# RMP_-_HALF_BRIDGE_0_0_2.net
KiCad netlist of a schematic drawn in EAGLE
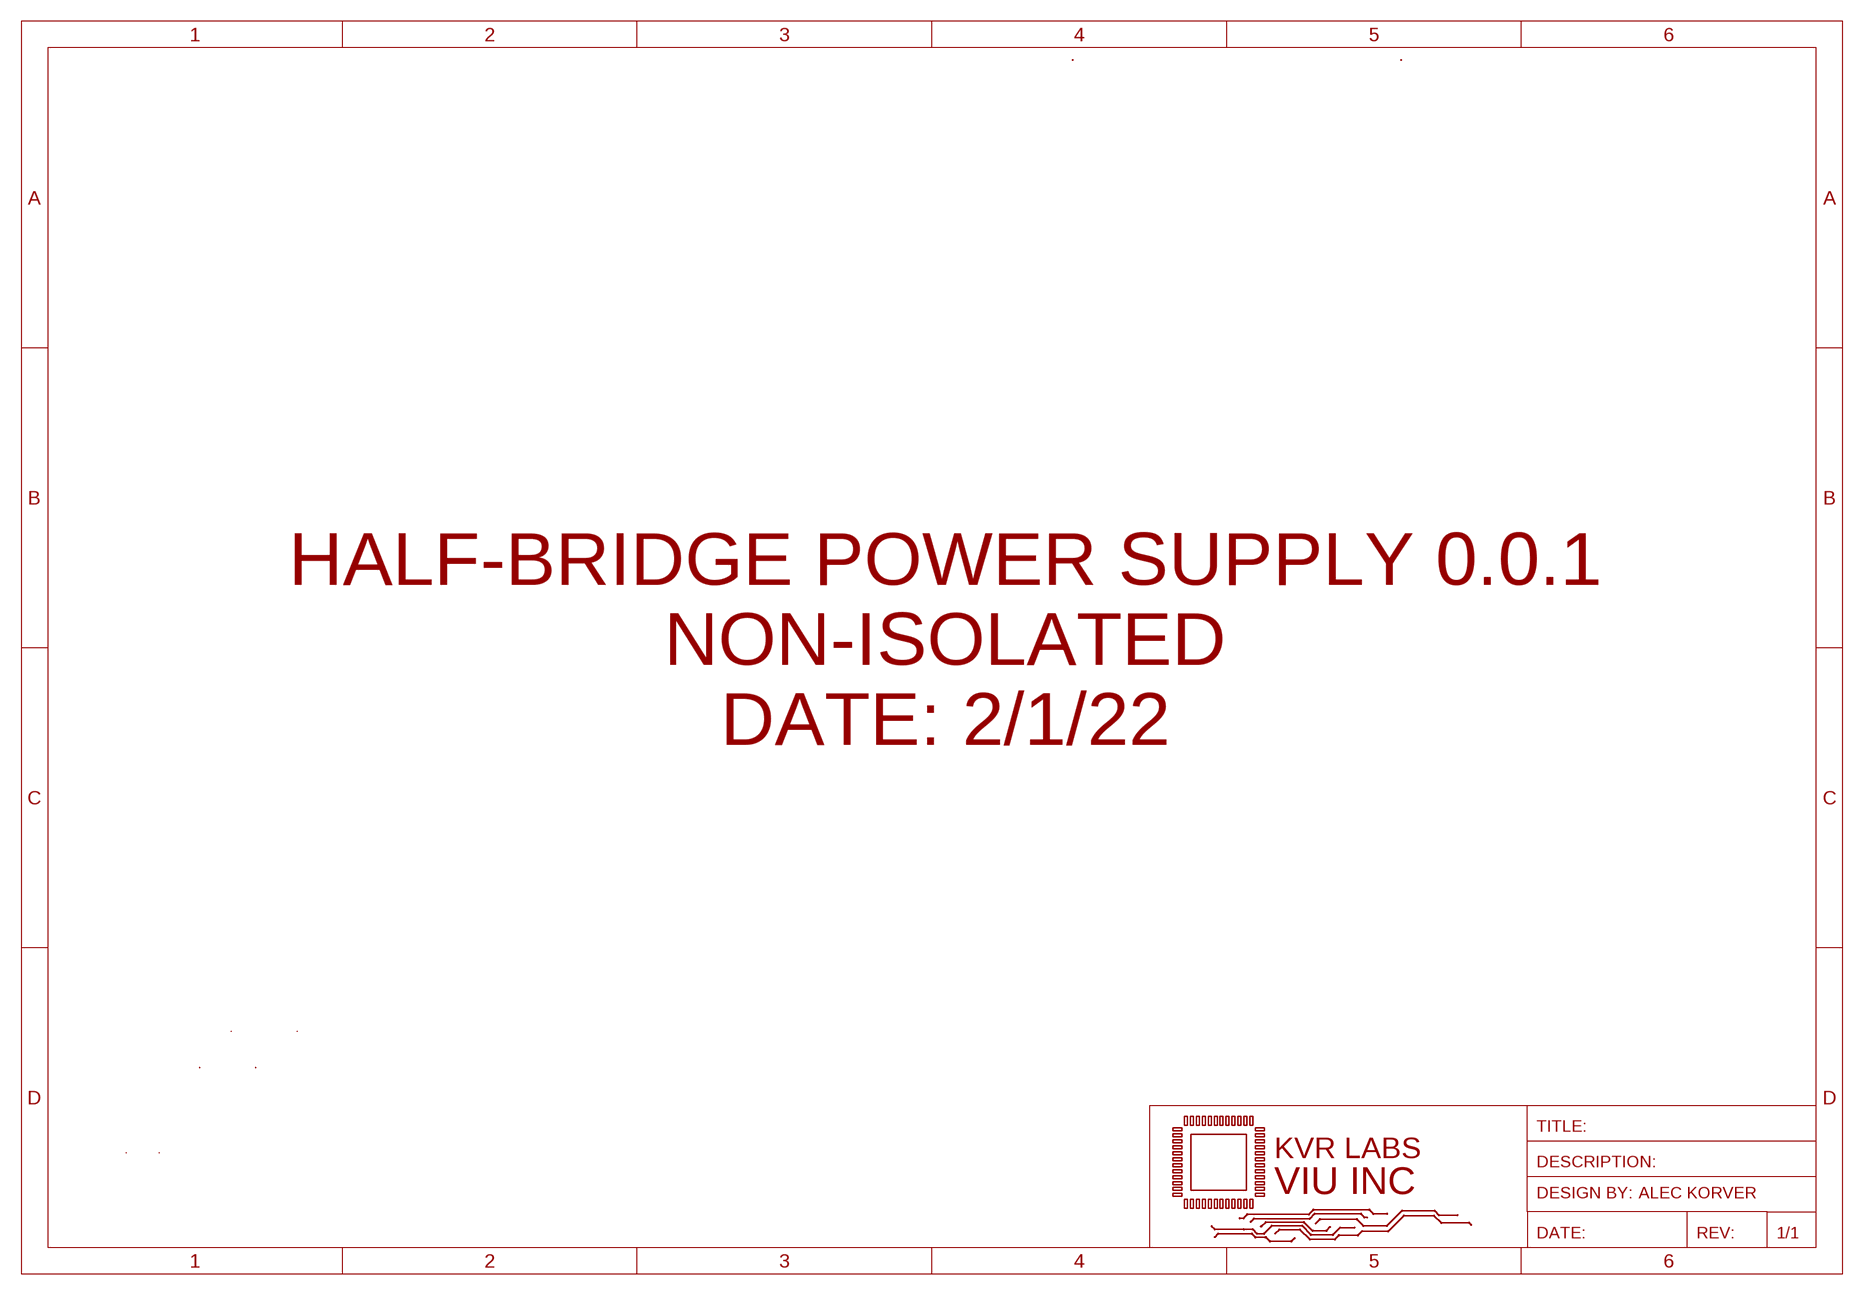
[diagram p0: schematic, sheet 1]
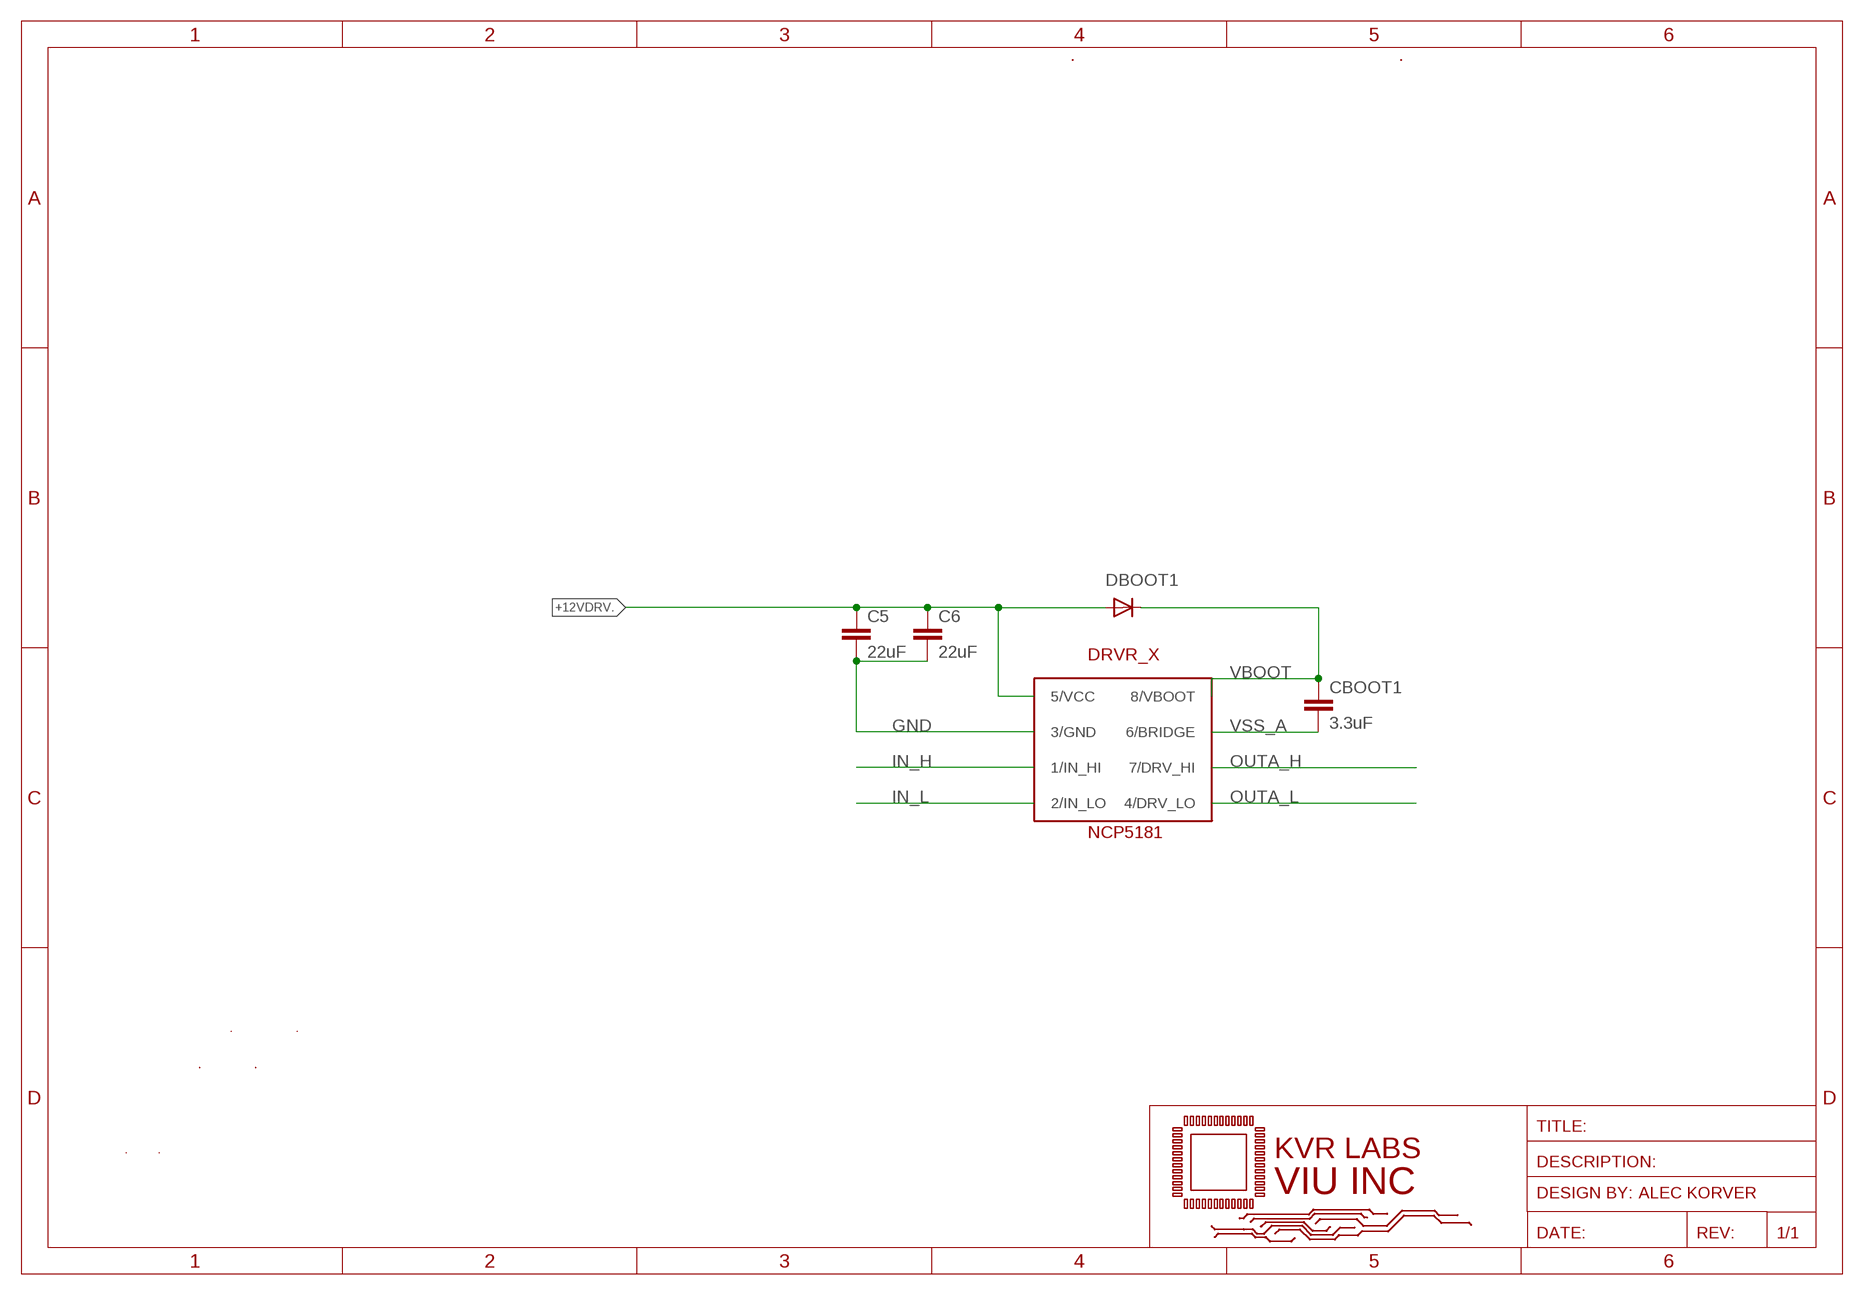
[diagram p1: schematic, sheet 2]
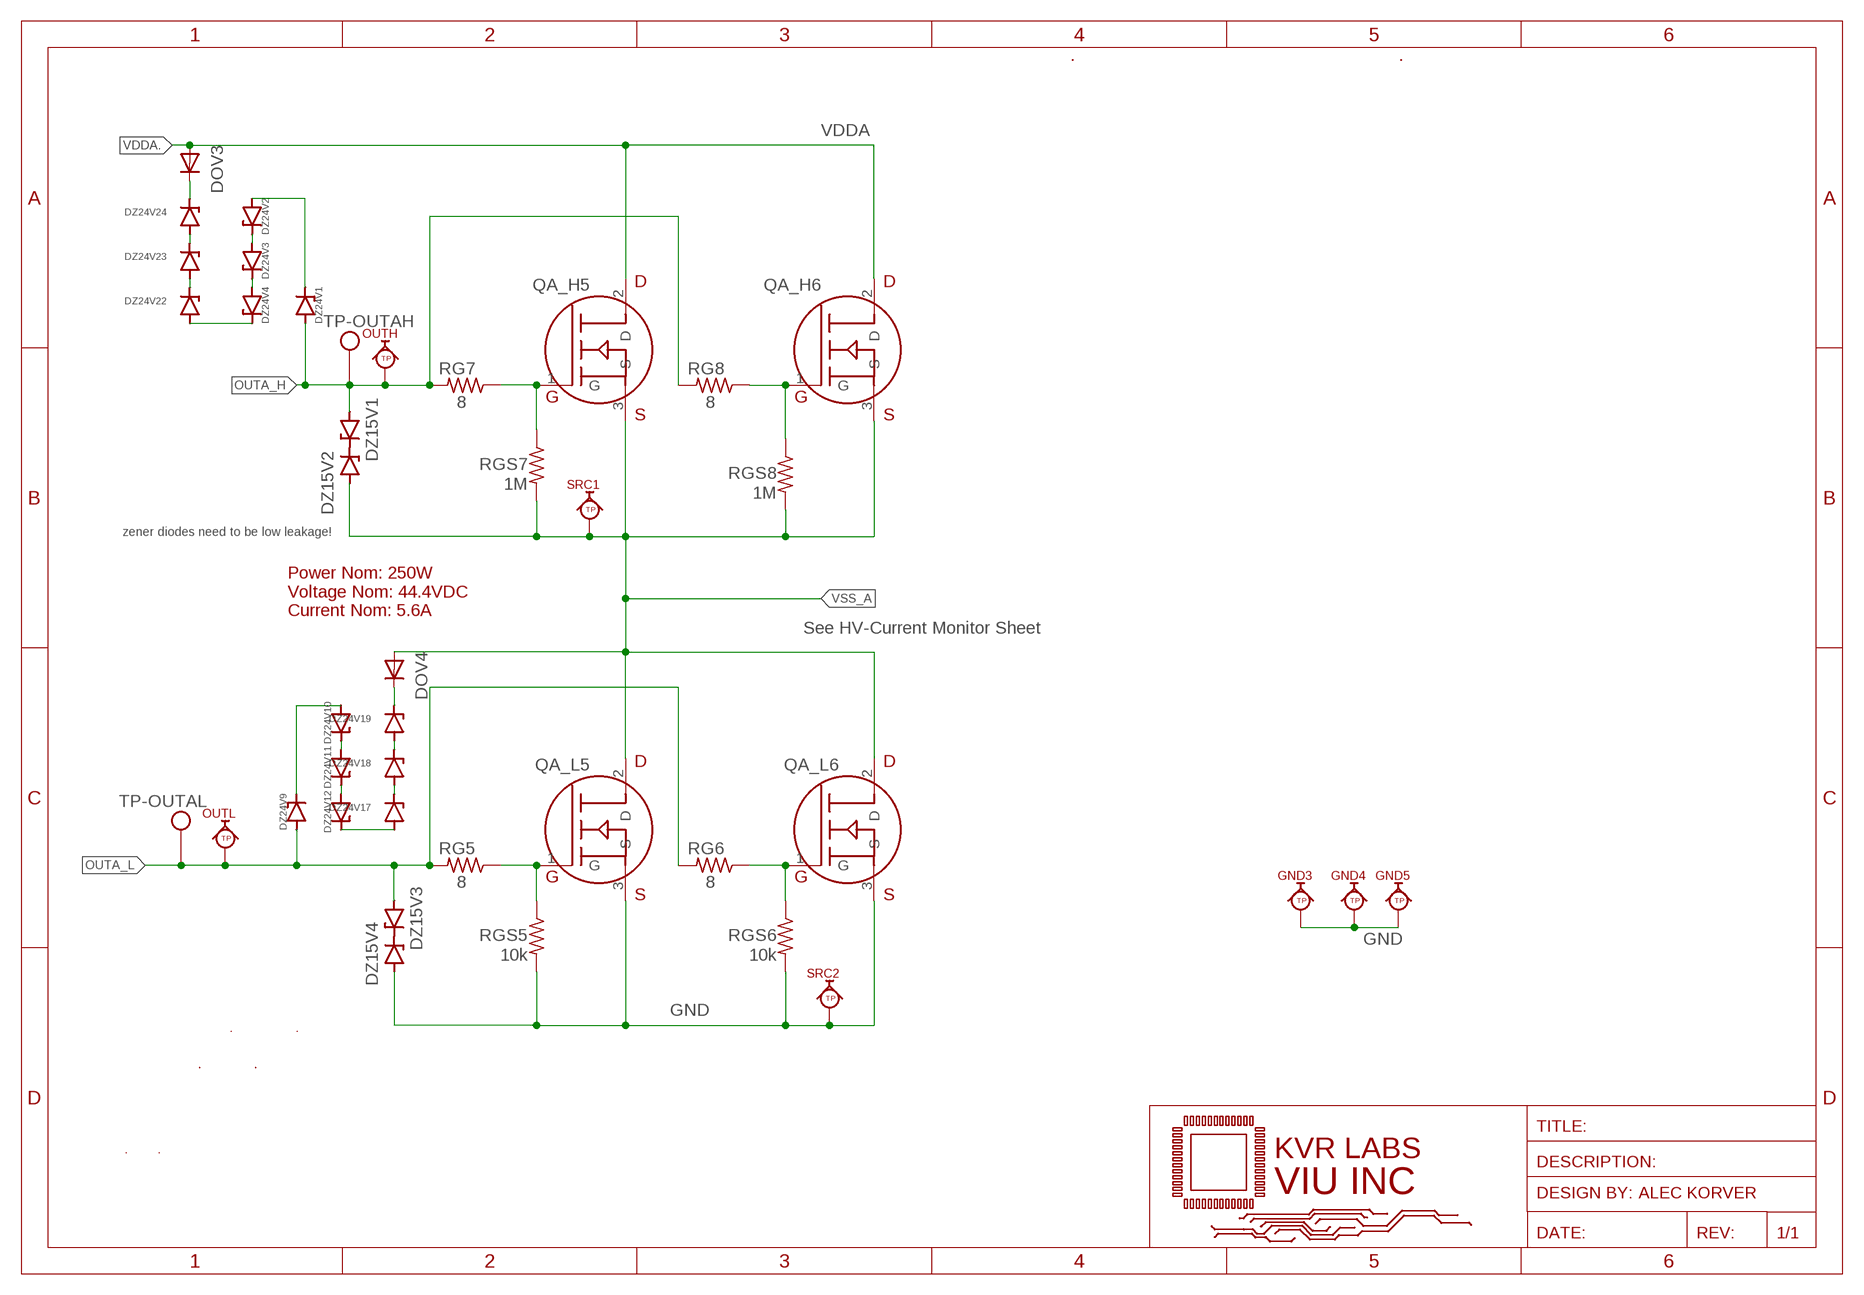
[diagram p2: schematic, sheet 3]
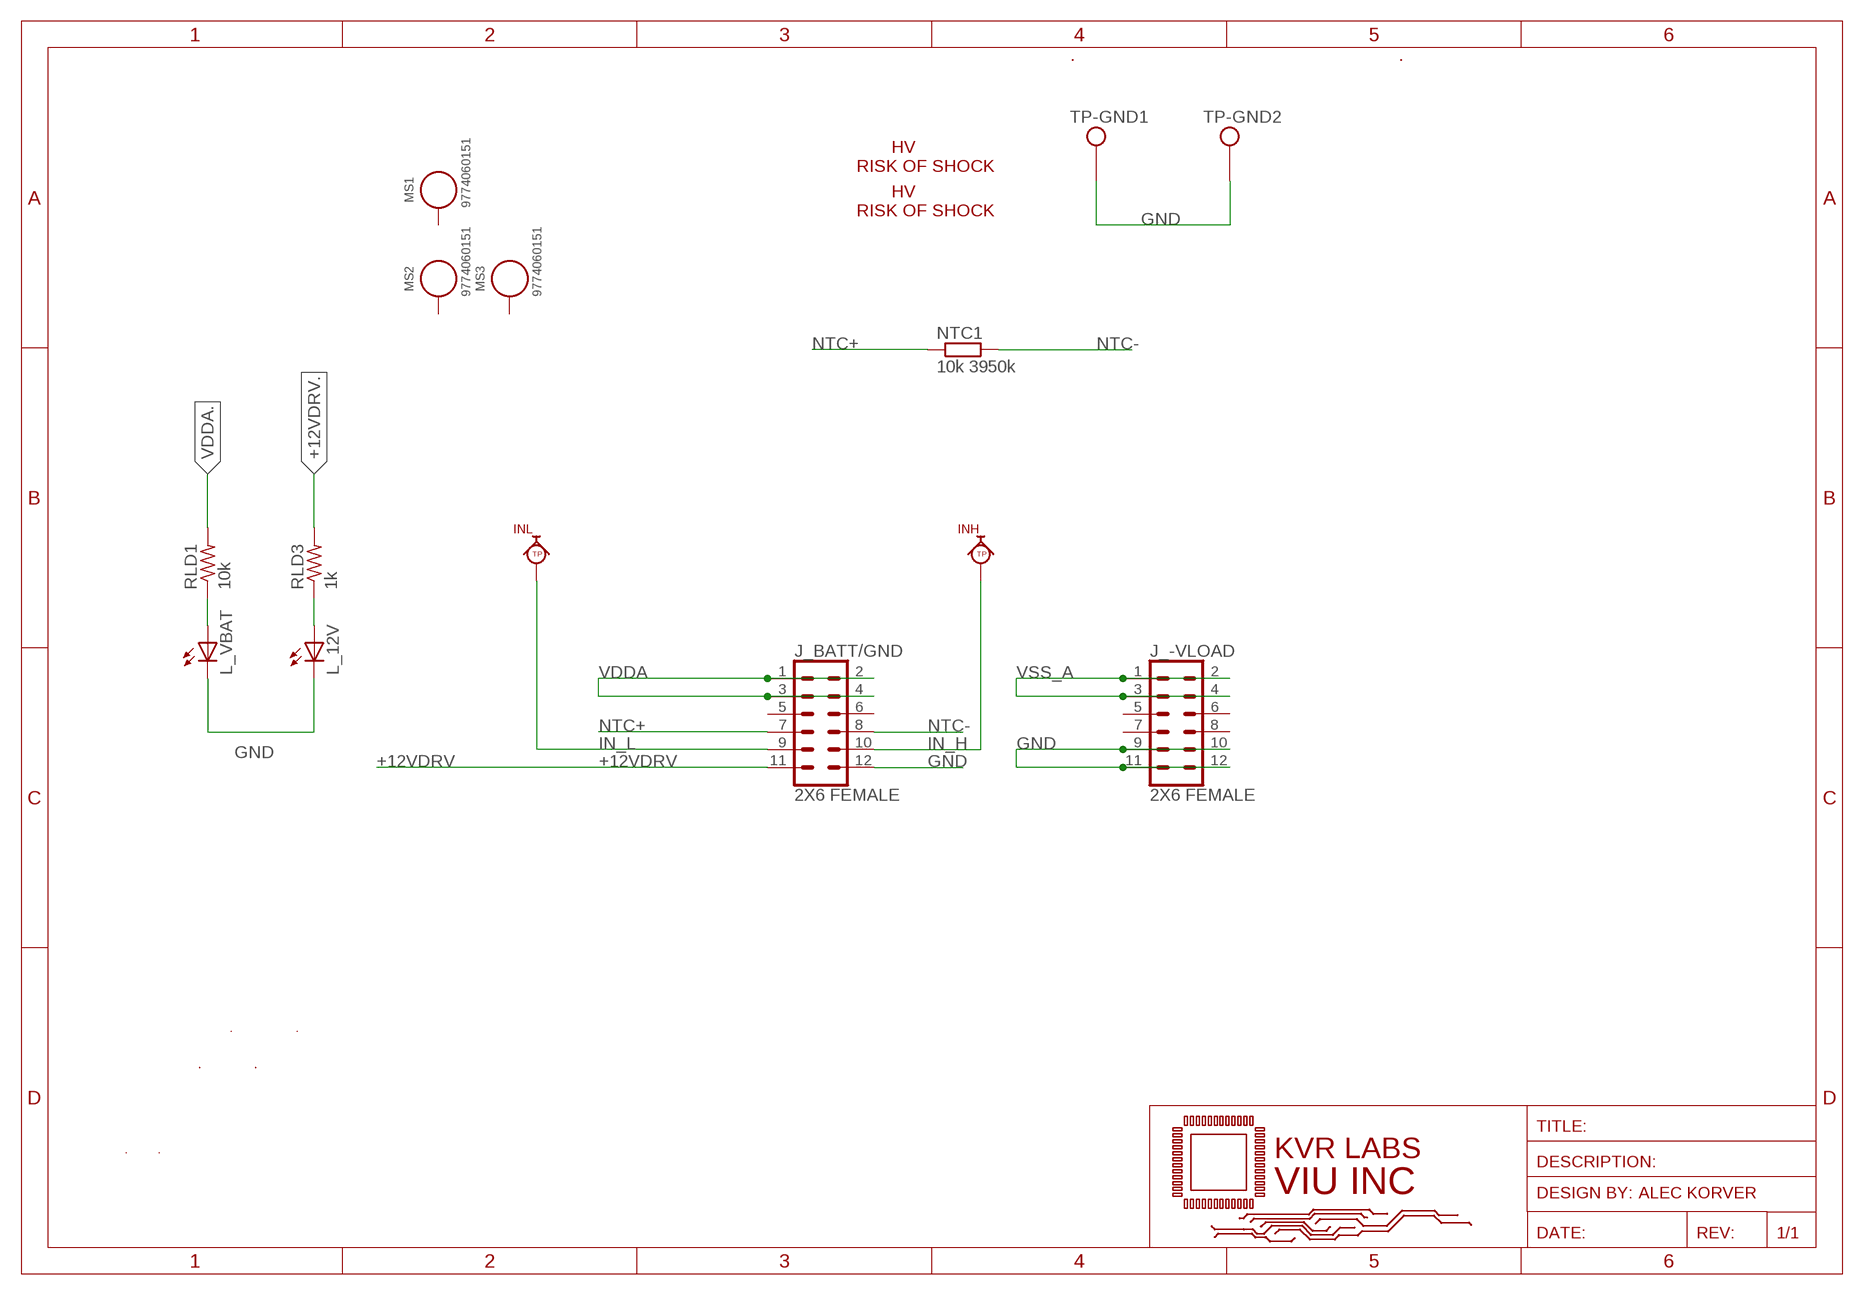
[diagram p3: schematic, sheet 4]
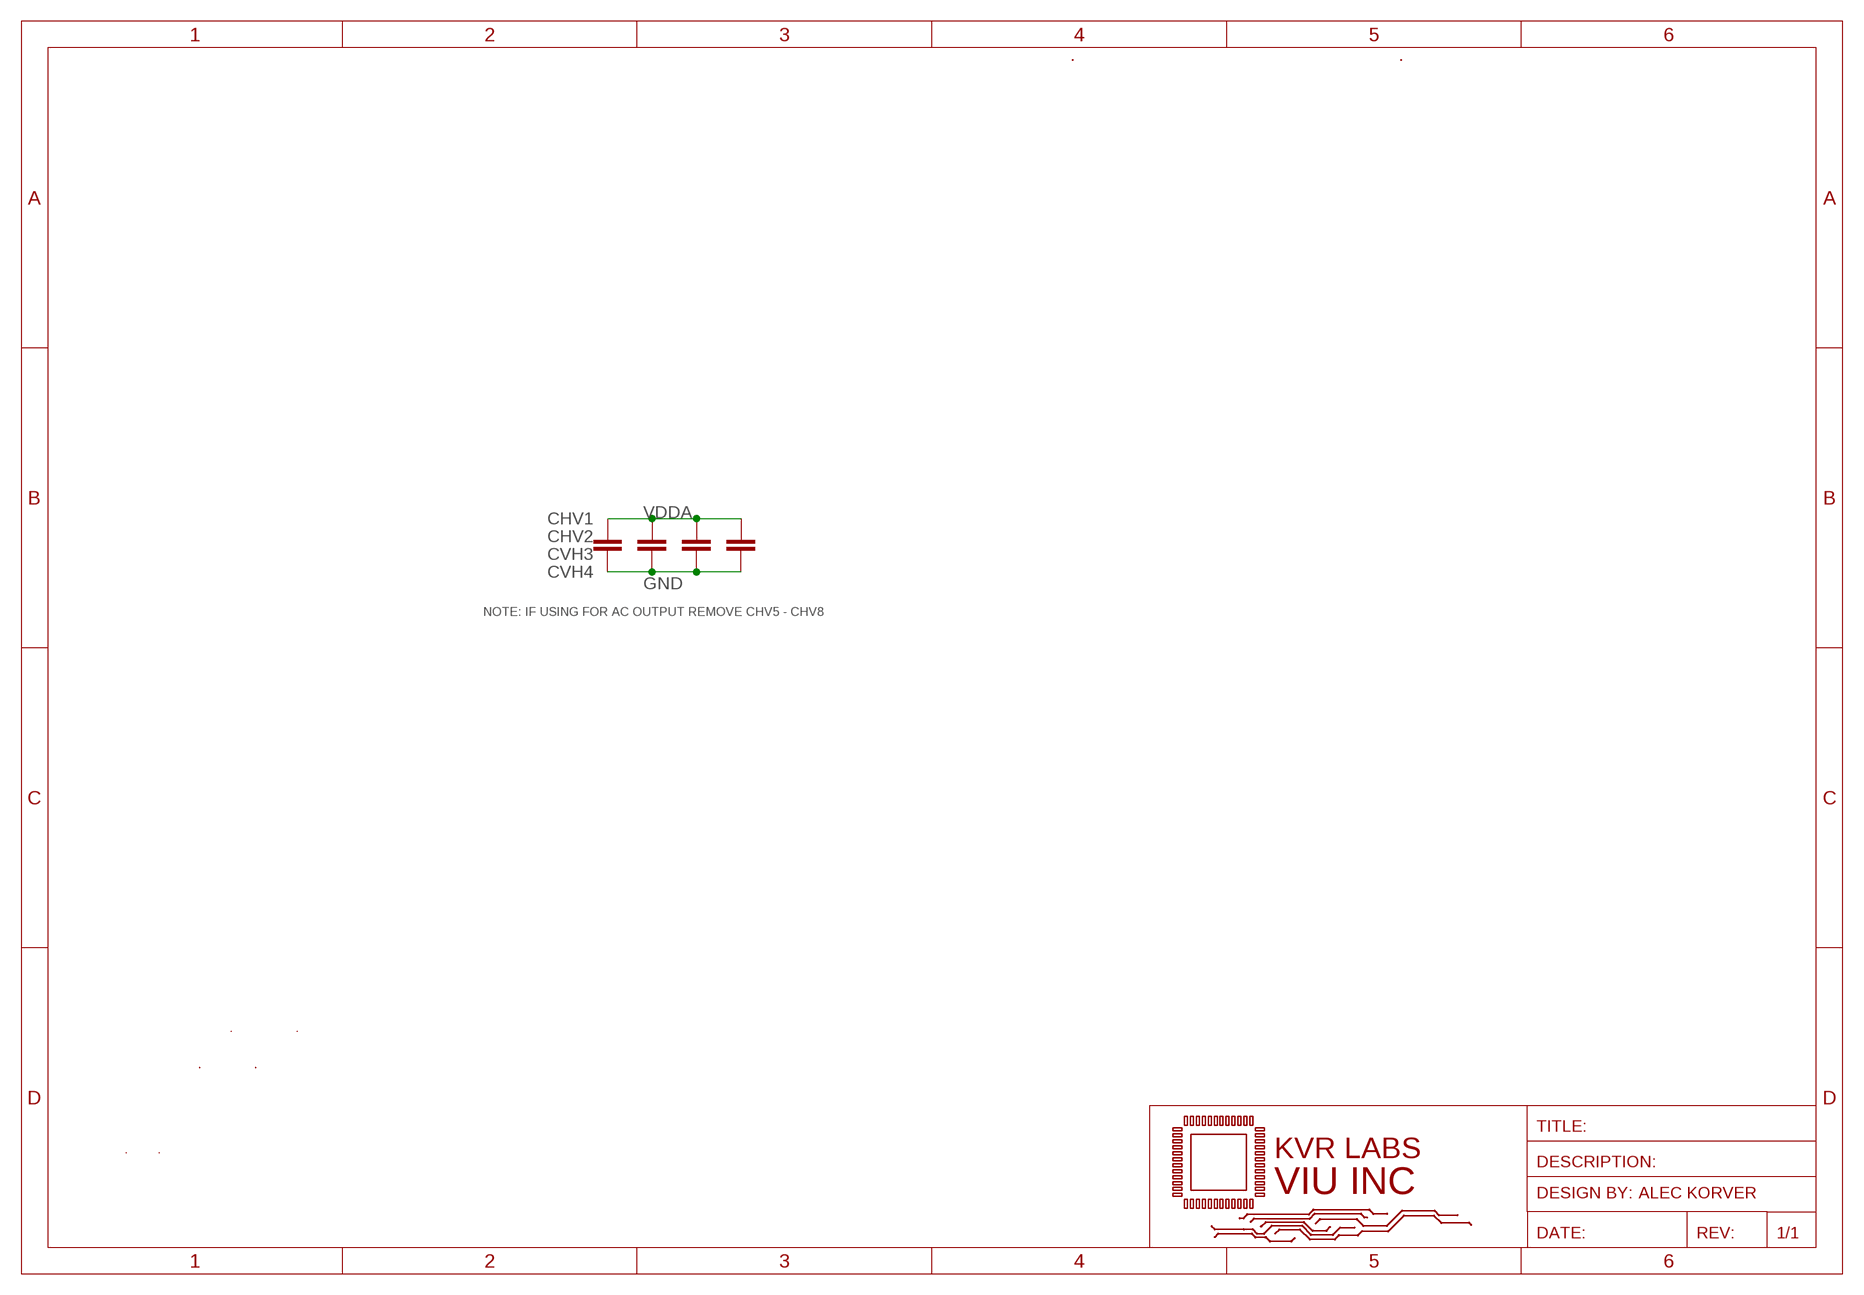
[diagram p4: schematic, sheet 5]

(export (version "E")
  (design (tool "Eeschema 10.0.6"))
  (components
    (comp (ref "INH")
      (value "KEYSTONE_5190_SMT")
      (footprint "eagle-import:KEYSTONE_5190_SMT")
      (libsource (lib "eagle-import") (part "KEYSTONE_5190_SMT"))
    )
    (comp (ref "INL")
      (value "KEYSTONE_5190_SMT")
      (footprint "eagle-import:KEYSTONE_5190_SMT")
      (libsource (lib "eagle-import") (part "KEYSTONE_5190_SMT"))
    )
    (comp (ref "J_-VLOAD")
      (value "2X6 FEMALE")
      (footprint "eagle-import:2X6")
      (fields (field (name "LCSC_PART") "DNP"))
      (libsource (lib "eagle-import") (part "CONN_06X2PTH_FEMALE"))
    )
    (comp (ref "J_BATT/GND")
      (value "2X6 FEMALE")
      (footprint "eagle-import:2X6")
      (fields (field (name "LCSC_PART") "DNP"))
      (libsource (lib "eagle-import") (part "CONN_06X2PTH_FEMALE"))
    )
    (comp (ref "L_12V")
      (value "LEDCHIPLED_1206")
      (footprint "eagle-import:CHIPLED_1206")
      (fields (field (name "LCSC_PART") "C434439"))
      (libsource (lib "eagle-import") (part "LEDCHIPLED_1206"))
    )
    (comp (ref "L_VBAT")
      (value "LEDCHIPLED_1206")
      (footprint "eagle-import:CHIPLED_1206")
      (fields (field (name "LCSC_PART") "C434439"))
      (libsource (lib "eagle-import") (part "LEDCHIPLED_1206"))
    )
    (comp (ref "MS1")
      (value "9774060151")
      (footprint "eagle-import:WA-SMSI_9774060151")
      (fields (field (name "LCSC_PART") "DNP"))
      (libsource (lib "eagle-import") (part "WA-SMSI_9774XXX151_9774060151"))
    )
    (comp (ref "MS2")
      (value "9774060151")
      (footprint "eagle-import:WA-SMSI_9774060151")
      (fields (field (name "LCSC_PART") "DNP"))
      (libsource (lib "eagle-import") (part "WA-SMSI_9774XXX151_9774060151"))
    )
    (comp (ref "MS3")
      (value "9774060151")
      (footprint "eagle-import:WA-SMSI_9774060151")
      (fields (field (name "LCSC_PART") "DNP"))
      (libsource (lib "eagle-import") (part "WA-SMSI_9774XXX151_9774060151"))
    )
    (comp (ref "NTC1")
      (value "10k 3950k")
      (footprint "eagle-import:R0805")
      (fields (field (name "LCSC_PART") "C95968"))
      (libsource (lib "eagle-import") (part "R-EU_R0805"))
    )
    (comp (ref "RLD1")
      (value "10k")
      (footprint "eagle-import:R1206")
      (fields (field (name "LCSC_PART") "C140407"))
      (libsource (lib "eagle-import") (part "R-US_R1206"))
    )
    (comp (ref "RLD3")
      (value "1k")
      (footprint "eagle-import:R1206")
      (fields (field (name "LCSC_PART") "C115421"))
      (libsource (lib "eagle-import") (part "R-US_R1206"))
    )
    (comp (ref "TP-GND1")
      (value "THM_TESTPOINT_5000_SERIES")
      (footprint "eagle-import:THM-TESTPOINT")
      (fields (field (name "LCSC_PART") "DNP"))
      (libsource (lib "eagle-import") (part "THM_TESTPOINT_5000_SERIES"))
    )
    (comp (ref "TP-GND2")
      (value "THM_TESTPOINT_5000_SERIES")
      (footprint "eagle-import:THM-TESTPOINT")
      (fields (field (name "LCSC_PART") "DNP"))
      (libsource (lib "eagle-import") (part "THM_TESTPOINT_5000_SERIES"))
    )
    (comp (ref "U$10")
      (value "ELECTRIC_SHOCK")
      (footprint "eagle-import:ELECTRIC_SHOCK")
      (fields (field (name "LCSC_PART") "DNP"))
      (libsource (lib "eagle-import") (part "ELECTRIC_SHOCK"))
    )
    (comp (ref "U$11")
      (value "ELECTRIC_SHOCK")
      (footprint "eagle-import:ELECTRIC_SHOCK")
      (fields (field (name "LCSC_PART") "DNP"))
      (libsource (lib "eagle-import") (part "ELECTRIC_SHOCK"))
    )
    (comp (ref "C5")
      (value "22uF")
      (footprint "eagle-import:C1206")
      (fields (field (name "LCSC_PART") "C77091"))
      (libsource (lib "eagle-import") (part "C-EUC1206"))
    )
    (comp (ref "C6")
      (value "22uF")
      (footprint "eagle-import:C1206")
      (fields (field (name "LCSC_PART") "C77091"))
      (libsource (lib "eagle-import") (part "C-EUC1206"))
    )
    (comp (ref "CBOOT1")
      (value "3.3uF")
      (footprint "eagle-import:C1812")
      (fields (field (name "LCSC_PART") "C342636"))
      (libsource (lib "eagle-import") (part "C-EUC1812"))
    )
    (comp (ref "DBOOT1")
      (value "DIODESMA")
      (footprint "eagle-import:SMADIODE")
      (fields (field (name "LCSC_PART") "C110531"))
      (libsource (lib "eagle-import") (part "DIODESMA"))
    )
    (comp (ref "DRVR_X")
      (value "NCP5181")
      (footprint "eagle-import:8-SOIC")
      (fields (field (name "LCSC_PART") "DNP"))
      (libsource (lib "eagle-import") (part "NCP5181"))
    )
    (comp (ref "DOV3")
      (value "DIODESMA")
      (footprint "eagle-import:SMADIODE")
      (fields (field (name "LCSC_PART") "C110531"))
      (libsource (lib "eagle-import") (part "DIODESMA"))
    )
    (comp (ref "DOV4")
      (value "DIODESMA")
      (footprint "eagle-import:SMADIODE")
      (fields (field (name "LCSC_PART") "C110531"))
      (libsource (lib "eagle-import") (part "DIODESMA"))
    )
    (comp (ref "DZ15V1")
      (value "NZH15B,115")
      (footprint "eagle-import:SODFL3718X115")
      (fields
        (field (name "MANUFACTURER") "ON Semiconductor ")
        (field (name "MPN") "MMSZ5240BT1G")
        (field (name "LCSC_PART") "C173428")
      )
      (libsource (lib "eagle-import") (part "ZENER_DO-219-AB(SOD123F)MMSZ5240BT"))
    )
    (comp (ref "DZ15V2")
      (value "NZH15B,115")
      (footprint "eagle-import:SODFL3718X115")
      (fields
        (field (name "MANUFACTURER") "ON Semiconductor ")
        (field (name "MPN") "MMSZ5240BT1G")
        (field (name "LCSC_PART") "C173428")
      )
      (libsource (lib "eagle-import") (part "ZENER_DO-219-AB(SOD123F)MMSZ5240BT"))
    )
    (comp (ref "DZ15V3")
      (value "NZH15B,115")
      (footprint "eagle-import:SODFL3718X115")
      (fields
        (field (name "MANUFACTURER") "ON Semiconductor ")
        (field (name "MPN") "MMSZ5240BT1G")
        (field (name "LCSC_PART") "C173428")
      )
      (libsource (lib "eagle-import") (part "ZENER_DO-219-AB(SOD123F)MMSZ5240BT"))
    )
    (comp (ref "DZ15V4")
      (value "NZH15B,115")
      (footprint "eagle-import:SODFL3718X115")
      (fields
        (field (name "MANUFACTURER") "ON Semiconductor ")
        (field (name "MPN") "MMSZ5240BT1G")
        (field (name "LCSC_PART") "C173428")
      )
      (libsource (lib "eagle-import") (part "ZENER_DO-219-AB(SOD123F)MMSZ5240BT"))
    )
    (comp (ref "DZ24V1")
      (value "NZH15B,115")
      (footprint "eagle-import:SODFL3718X115")
      (fields
        (field (name "MANUFACTURER") "ON Semiconductor ")
        (field (name "MPN") "MMSZ5240BT1G")
        (field (name "LCSC_PART") "C266572")
      )
      (libsource (lib "eagle-import") (part "ZENER_DO-219-AB(SOD123F)MMSZ5240BT"))
    )
    (comp (ref "DZ24V2")
      (value "NZH15B,115")
      (footprint "eagle-import:SODFL3718X115")
      (fields
        (field (name "MANUFACTURER") "ON Semiconductor ")
        (field (name "MPN") "MMSZ5240BT1G")
        (field (name "LCSC_PART") "C266572")
      )
      (libsource (lib "eagle-import") (part "ZENER_DO-219-AB(SOD123F)MMSZ5240BT"))
    )
    (comp (ref "DZ24V3")
      (value "NZH15B,115")
      (footprint "eagle-import:SODFL3718X115")
      (fields
        (field (name "MANUFACTURER") "ON Semiconductor ")
        (field (name "MPN") "MMSZ5240BT1G")
        (field (name "LCSC_PART") "C266572")
      )
      (libsource (lib "eagle-import") (part "ZENER_DO-219-AB(SOD123F)MMSZ5240BT"))
    )
    (comp (ref "DZ24V4")
      (value "NZH15B,115")
      (footprint "eagle-import:SODFL3718X115")
      (fields
        (field (name "MANUFACTURER") "ON Semiconductor ")
        (field (name "MPN") "MMSZ5240BT1G")
        (field (name "LCSC_PART") "C266572")
      )
      (libsource (lib "eagle-import") (part "ZENER_DO-219-AB(SOD123F)MMSZ5240BT"))
    )
    (comp (ref "DZ24V9")
      (value "NZH15B,115")
      (footprint "eagle-import:SODFL3718X115")
      (fields
        (field (name "MANUFACTURER") "ON Semiconductor ")
        (field (name "MPN") "MMSZ5240BT1G")
        (field (name "LCSC_PART") "C266572")
      )
      (libsource (lib "eagle-import") (part "ZENER_DO-219-AB(SOD123F)MMSZ5240BT"))
    )
    (comp (ref "DZ24V10")
      (value "NZH15B,115")
      (footprint "eagle-import:SODFL3718X115")
      (fields
        (field (name "MANUFACTURER") "ON Semiconductor ")
        (field (name "MPN") "MMSZ5240BT1G")
        (field (name "LCSC_PART") "C266572")
      )
      (libsource (lib "eagle-import") (part "ZENER_DO-219-AB(SOD123F)MMSZ5240BT"))
    )
    (comp (ref "DZ24V11")
      (value "NZH15B,115")
      (footprint "eagle-import:SODFL3718X115")
      (fields
        (field (name "MANUFACTURER") "ON Semiconductor ")
        (field (name "MPN") "MMSZ5240BT1G")
        (field (name "LCSC_PART") "C266572")
      )
      (libsource (lib "eagle-import") (part "ZENER_DO-219-AB(SOD123F)MMSZ5240BT"))
    )
    (comp (ref "DZ24V12")
      (value "NZH15B,115")
      (footprint "eagle-import:SODFL3718X115")
      (fields
        (field (name "MANUFACTURER") "ON Semiconductor ")
        (field (name "MPN") "MMSZ5240BT1G")
        (field (name "LCSC_PART") "C266572")
      )
      (libsource (lib "eagle-import") (part "ZENER_DO-219-AB(SOD123F)MMSZ5240BT"))
    )
    (comp (ref "DZ24V17")
      (value "NZH15B,115")
      (footprint "eagle-import:SODFL3718X115")
      (fields
        (field (name "MANUFACTURER") "ON Semiconductor ")
        (field (name "MPN") "MMSZ5240BT1G")
        (field (name "LCSC_PART") "C266572")
      )
      (libsource (lib "eagle-import") (part "ZENER_DO-219-AB(SOD123F)MMSZ5240BT"))
    )
    (comp (ref "DZ24V18")
      (value "NZH15B,115")
      (footprint "eagle-import:SODFL3718X115")
      (fields
        (field (name "MANUFACTURER") "ON Semiconductor ")
        (field (name "MPN") "MMSZ5240BT1G")
        (field (name "LCSC_PART") "C266572")
      )
      (libsource (lib "eagle-import") (part "ZENER_DO-219-AB(SOD123F)MMSZ5240BT"))
    )
    (comp (ref "DZ24V19")
      (value "NZH15B,115")
      (footprint "eagle-import:SODFL3718X115")
      (fields
        (field (name "MANUFACTURER") "ON Semiconductor ")
        (field (name "MPN") "MMSZ5240BT1G")
        (field (name "LCSC_PART") "C266572")
      )
      (libsource (lib "eagle-import") (part "ZENER_DO-219-AB(SOD123F)MMSZ5240BT"))
    )
    (comp (ref "DZ24V22")
      (value "NZH15B,115")
      (footprint "eagle-import:SODFL3718X115")
      (fields
        (field (name "MANUFACTURER") "ON Semiconductor ")
        (field (name "MPN") "MMSZ5240BT1G")
        (field (name "LCSC_PART") "C266572")
      )
      (libsource (lib "eagle-import") (part "ZENER_DO-219-AB(SOD123F)MMSZ5240BT"))
    )
    (comp (ref "DZ24V23")
      (value "NZH15B,115")
      (footprint "eagle-import:SODFL3718X115")
      (fields
        (field (name "MANUFACTURER") "ON Semiconductor ")
        (field (name "MPN") "MMSZ5240BT1G")
        (field (name "LCSC_PART") "C266572")
      )
      (libsource (lib "eagle-import") (part "ZENER_DO-219-AB(SOD123F)MMSZ5240BT"))
    )
    (comp (ref "DZ24V24")
      (value "NZH15B,115")
      (footprint "eagle-import:SODFL3718X115")
      (fields
        (field (name "MANUFACTURER") "ON Semiconductor ")
        (field (name "MPN") "MMSZ5240BT1G")
        (field (name "LCSC_PART") "C266572")
      )
      (libsource (lib "eagle-import") (part "ZENER_DO-219-AB(SOD123F)MMSZ5240BT"))
    )
    (comp (ref "GND3")
      (value "KEYSTONE_5190_SMT")
      (footprint "eagle-import:KEYSTONE_5190_SMT")
      (libsource (lib "eagle-import") (part "KEYSTONE_5190_SMT"))
    )
    (comp (ref "GND4")
      (value "KEYSTONE_5190_SMT")
      (footprint "eagle-import:KEYSTONE_5190_SMT")
      (libsource (lib "eagle-import") (part "KEYSTONE_5190_SMT"))
    )
    (comp (ref "GND5")
      (value "KEYSTONE_5190_SMT")
      (footprint "eagle-import:KEYSTONE_5190_SMT")
      (libsource (lib "eagle-import") (part "KEYSTONE_5190_SMT"))
    )
    (comp (ref "OUTH")
      (value "KEYSTONE_5190_SMT")
      (footprint "eagle-import:KEYSTONE_5190_SMT")
      (libsource (lib "eagle-import") (part "KEYSTONE_5190_SMT"))
    )
    (comp (ref "OUTL")
      (value "KEYSTONE_5190_SMT")
      (footprint "eagle-import:KEYSTONE_5190_SMT")
      (libsource (lib "eagle-import") (part "KEYSTONE_5190_SMT"))
    )
    (comp (ref "QA_H5")
      (value "IPB60R060P7ATMA1")
      (footprint "eagle-import:D2PACK")
      (fields (field (name "LCSC_PART") "DNP"))
      (libsource (lib "eagle-import") (part "IPB60R060P7ATMA1"))
    )
    (comp (ref "QA_H6")
      (value "IPB60R060P7ATMA1")
      (footprint "eagle-import:D2PACK")
      (fields (field (name "LCSC_PART") "DNP"))
      (libsource (lib "eagle-import") (part "IPB60R060P7ATMA1"))
    )
    (comp (ref "QA_L5")
      (value "IPB60R060P7ATMA1")
      (footprint "eagle-import:D2PACK")
      (fields (field (name "LCSC_PART") "DNP"))
      (libsource (lib "eagle-import") (part "IPB60R060P7ATMA1"))
    )
    (comp (ref "QA_L6")
      (value "IPB60R060P7ATMA1")
      (footprint "eagle-import:D2PACK")
      (fields (field (name "LCSC_PART") "DNP"))
      (libsource (lib "eagle-import") (part "IPB60R060P7ATMA1"))
    )
    (comp (ref "RG5")
      (value "8")
      (footprint "eagle-import:R1206")
      (fields (field (name "LCSC_PART") "C118070"))
      (libsource (lib "eagle-import") (part "R-US_R1206"))
    )
    (comp (ref "RG6")
      (value "8")
      (footprint "eagle-import:R1206")
      (fields (field (name "LCSC_PART") "C118070"))
      (libsource (lib "eagle-import") (part "R-US_R1206"))
    )
    (comp (ref "RG7")
      (value "8")
      (footprint "eagle-import:R1206")
      (fields (field (name "LCSC_PART") "C118070"))
      (libsource (lib "eagle-import") (part "R-US_R1206"))
    )
    (comp (ref "RG8")
      (value "8")
      (footprint "eagle-import:R1206")
      (fields (field (name "LCSC_PART") "C118070"))
      (libsource (lib "eagle-import") (part "R-US_R1206"))
    )
    (comp (ref "RGS5")
      (value "10k")
      (footprint "eagle-import:R1206")
      (fields (field (name "LCSC_PART") "C140407"))
      (libsource (lib "eagle-import") (part "R-US_R1206"))
    )
    (comp (ref "RGS6")
      (value "10k")
      (footprint "eagle-import:R1206")
      (fields (field (name "LCSC_PART") "C140407"))
      (libsource (lib "eagle-import") (part "R-US_R1206"))
    )
    (comp (ref "RGS7")
      (value "1M")
      (footprint "eagle-import:R1206")
      (fields (field (name "LCSC_PART") "C105578"))
      (libsource (lib "eagle-import") (part "R-US_R1206"))
    )
    (comp (ref "RGS8")
      (value "1M")
      (footprint "eagle-import:R1206")
      (fields (field (name "LCSC_PART") "C105578"))
      (libsource (lib "eagle-import") (part "R-US_R1206"))
    )
    (comp (ref "SRC1")
      (value "KEYSTONE_5190_SMT")
      (footprint "eagle-import:KEYSTONE_5190_SMT")
      (libsource (lib "eagle-import") (part "KEYSTONE_5190_SMT"))
    )
    (comp (ref "SRC2")
      (value "KEYSTONE_5190_SMT")
      (footprint "eagle-import:KEYSTONE_5190_SMT")
      (libsource (lib "eagle-import") (part "KEYSTONE_5190_SMT"))
    )
    (comp (ref "TP-OUTAH")
      (value "THM_TESTPOINT_5000_SERIES")
      (footprint "eagle-import:THM-TESTPOINT")
      (fields (field (name "LCSC_PART") "DNP"))
      (libsource (lib "eagle-import") (part "THM_TESTPOINT_5000_SERIES"))
    )
    (comp (ref "TP-OUTAL")
      (value "THM_TESTPOINT_5000_SERIES")
      (footprint "eagle-import:THM-TESTPOINT")
      (fields (field (name "LCSC_PART") "DNP"))
      (libsource (lib "eagle-import") (part "THM_TESTPOINT_5000_SERIES"))
    )
    (comp (ref "CHV1")
      (value "3.3uF, 100V")
      (footprint "eagle-import:C2220K")
      (fields (field (name "LCSC_PART") "C342270"))
      (libsource (lib "eagle-import") (part "C-EUC2220K"))
    )
    (comp (ref "CHV2")
      (value "3.3uF, 100V")
      (footprint "eagle-import:C2220K")
      (fields (field (name "LCSC_PART") "C342270"))
      (libsource (lib "eagle-import") (part "C-EUC2220K"))
    )
    (comp (ref "CVH3")
      (value "3.3uF, 100V")
      (footprint "eagle-import:C2220K")
      (fields (field (name "LCSC_PART") "C342270"))
      (libsource (lib "eagle-import") (part "C-EUC2220K"))
    )
    (comp (ref "CVH4")
      (value "3.3uF, 100V")
      (footprint "eagle-import:C2220K")
      (fields (field (name "LCSC_PART") "C342270"))
      (libsource (lib "eagle-import") (part "C-EUC2220K"))
    )
  )
  (nets
    (net (code "1") (name "+12VDRV") (class "Default")
      (node (ref "C5") (pin "1") (pinfunction "1_1") (pintype "passive"))
      (node (ref "C6") (pin "1") (pinfunction "1_1") (pintype "passive"))
      (node (ref "DBOOT1") (pin "A") (pinfunction "A_A") (pintype "passive"))
      (node (ref "DRVR_X") (pin "5") (pinfunction "5/VCC_5") (pintype "bidirectional"))
      (node (ref "J_BATT/GND") (pin "11") (pinfunction "11_11") (pintype "passive"))
      (node (ref "RLD3") (pin "2") (pinfunction "2_2") (pintype "passive"))
    )
    (net (code "2") (name "GND") (class "Default")
      (node (ref "C5") (pin "2") (pinfunction "2_2") (pintype "passive"))
      (node (ref "C6") (pin "2") (pinfunction "2_2") (pintype "passive"))
      (node (ref "CHV1") (pin "2") (pinfunction "2_2") (pintype "passive"))
      (node (ref "CHV2") (pin "2") (pinfunction "2_2") (pintype "passive"))
      (node (ref "CVH3") (pin "2") (pinfunction "2_2") (pintype "passive"))
      (node (ref "CVH4") (pin "2") (pinfunction "2_2") (pintype "passive"))
      (node (ref "DRVR_X") (pin "3") (pinfunction "3/GND_3") (pintype "bidirectional"))
      (node (ref "DZ15V4") (pin "2") (pinfunction "A_2") (pintype "passive"))
      (node (ref "GND3") (pin "P$1") (pinfunction "P$1_P$1") (pintype "bidirectional"))
      (node (ref "GND4") (pin "P$1") (pinfunction "P$1_P$1") (pintype "bidirectional"))
      (node (ref "GND5") (pin "P$1") (pinfunction "P$1_P$1") (pintype "bidirectional"))
      (node (ref "J_-VLOAD") (pin "10") (pinfunction "10_10") (pintype "passive"))
      (node (ref "J_-VLOAD") (pin "11") (pinfunction "11_11") (pintype "passive"))
      (node (ref "J_-VLOAD") (pin "12") (pinfunction "12_12") (pintype "passive"))
      (node (ref "J_-VLOAD") (pin "9") (pinfunction "9_9") (pintype "passive"))
      (node (ref "J_BATT/GND") (pin "12") (pinfunction "12_12") (pintype "passive"))
      (node (ref "L_12V") (pin "C") (pinfunction "C_C") (pintype "passive"))
      (node (ref "L_VBAT") (pin "C") (pinfunction "C_C") (pintype "passive"))
      (node (ref "QA_L5") (pin "3") (pinfunction "S_3") (pintype "bidirectional"))
      (node (ref "QA_L6") (pin "3") (pinfunction "S_3") (pintype "bidirectional"))
      (node (ref "RGS5") (pin "2") (pinfunction "2_2") (pintype "passive"))
      (node (ref "RGS6") (pin "2") (pinfunction "2_2") (pintype "passive"))
      (node (ref "SRC2") (pin "P$1") (pinfunction "P$1_P$1") (pintype "bidirectional"))
      (node (ref "TP-GND1") (pin "P1") (pinfunction "P$1_P1") (pintype "bidirectional"))
      (node (ref "TP-GND2") (pin "P1") (pinfunction "P$1_P1") (pintype "bidirectional"))
    )
    (net (code "3") (name "IN_H") (class "Default")
      (node (ref "DRVR_X") (pin "1") (pinfunction "1/IN_HI_1") (pintype "bidirectional"))
      (node (ref "INH") (pin "P$1") (pinfunction "P$1_P$1") (pintype "bidirectional"))
      (node (ref "J_BATT/GND") (pin "10") (pinfunction "10_10") (pintype "passive"))
    )
    (net (code "4") (name "IN_L") (class "Default")
      (node (ref "DRVR_X") (pin "2") (pinfunction "2/IN_LO_2") (pintype "bidirectional"))
      (node (ref "INL") (pin "P$1") (pinfunction "P$1_P$1") (pintype "bidirectional"))
      (node (ref "J_BATT/GND") (pin "9") (pinfunction "9_9") (pintype "passive"))
    )
    (net (code "5") (name "NTC+") (class "Default")
      (node (ref "J_BATT/GND") (pin "7") (pinfunction "7_7") (pintype "passive"))
      (node (ref "NTC1") (pin "1") (pinfunction "1_1") (pintype "passive"))
    )
    (net (code "6") (name "NTC-") (class "Default")
      (node (ref "J_BATT/GND") (pin "8") (pinfunction "8_8") (pintype "passive"))
      (node (ref "NTC1") (pin "2") (pinfunction "2_2") (pintype "passive"))
    )
    (net (code "7") (name "Net-(DZ15V1-C)") (class "Default")
      (node (ref "DZ15V1") (pin "1") (pinfunction "C_1") (pintype "passive"))
      (node (ref "DZ15V2") (pin "1") (pinfunction "C_1") (pintype "passive"))
    )
    (net (code "8") (name "Net-(DZ15V3-C)") (class "Default")
      (node (ref "DZ15V3") (pin "1") (pinfunction "C_1") (pintype "passive"))
      (node (ref "DZ15V4") (pin "1") (pinfunction "C_1") (pintype "passive"))
    )
    (net (code "9") (name "Net-(DZ24V1-C)") (class "Default")
      (node (ref "DZ24V1") (pin "1") (pinfunction "C_1") (pintype "passive"))
      (node (ref "DZ24V2") (pin "2") (pinfunction "A_2") (pintype "passive"))
    )
    (net (code "10") (name "Net-(DZ24V2-C)") (class "Default")
      (node (ref "DZ24V2") (pin "1") (pinfunction "C_1") (pintype "passive"))
      (node (ref "DZ24V3") (pin "2") (pinfunction "A_2") (pintype "passive"))
    )
    (net (code "11") (name "Net-(DZ24V3-C)") (class "Default")
      (node (ref "DZ24V3") (pin "1") (pinfunction "C_1") (pintype "passive"))
      (node (ref "DZ24V4") (pin "2") (pinfunction "A_2") (pintype "passive"))
    )
    (net (code "12") (name "Net-(DZ24V10-A)") (class "Default")
      (node (ref "DZ24V10") (pin "2") (pinfunction "A_2") (pintype "passive"))
      (node (ref "DZ24V9") (pin "1") (pinfunction "C_1") (pintype "passive"))
    )
    (net (code "13") (name "Net-(DZ24V10-C)") (class "Default")
      (node (ref "DZ24V10") (pin "1") (pinfunction "C_1") (pintype "passive"))
      (node (ref "DZ24V11") (pin "2") (pinfunction "A_2") (pintype "passive"))
    )
    (net (code "14") (name "Net-(DZ24V11-C)") (class "Default")
      (node (ref "DZ24V11") (pin "1") (pinfunction "C_1") (pintype "passive"))
      (node (ref "DZ24V12") (pin "2") (pinfunction "A_2") (pintype "passive"))
    )
    (net (code "15") (name "Net-(DZ24V12-C)") (class "Default")
      (node (ref "DZ24V12") (pin "1") (pinfunction "C_1") (pintype "passive"))
      (node (ref "DZ24V17") (pin "2") (pinfunction "A_2") (pintype "passive"))
    )
    (net (code "16") (name "Net-(DZ24V17-C)") (class "Default")
      (node (ref "DZ24V17") (pin "1") (pinfunction "C_1") (pintype "passive"))
      (node (ref "DZ24V18") (pin "2") (pinfunction "A_2") (pintype "passive"))
    )
    (net (code "17") (name "Net-(DZ24V18-C)") (class "Default")
      (node (ref "DZ24V18") (pin "1") (pinfunction "C_1") (pintype "passive"))
      (node (ref "DZ24V19") (pin "2") (pinfunction "A_2") (pintype "passive"))
    )
    (net (code "18") (name "Net-(DZ24V19-C)") (class "Default")
      (node (ref "DOV4") (pin "C") (pinfunction "C_C") (pintype "passive"))
      (node (ref "DZ24V19") (pin "1") (pinfunction "C_1") (pintype "passive"))
    )
    (net (code "19") (name "Net-(DZ24V22-A)") (class "Default")
      (node (ref "DZ24V22") (pin "2") (pinfunction "A_2") (pintype "passive"))
      (node (ref "DZ24V4") (pin "1") (pinfunction "C_1") (pintype "passive"))
    )
    (net (code "20") (name "Net-(DZ24V22-C)") (class "Default")
      (node (ref "DZ24V22") (pin "1") (pinfunction "C_1") (pintype "passive"))
      (node (ref "DZ24V23") (pin "2") (pinfunction "A_2") (pintype "passive"))
    )
    (net (code "21") (name "Net-(DZ24V23-C)") (class "Default")
      (node (ref "DZ24V23") (pin "1") (pinfunction "C_1") (pintype "passive"))
      (node (ref "DZ24V24") (pin "2") (pinfunction "A_2") (pintype "passive"))
    )
    (net (code "22") (name "Net-(DZ24V24-C)") (class "Default")
      (node (ref "DOV3") (pin "C") (pinfunction "C_C") (pintype "passive"))
      (node (ref "DZ24V24") (pin "1") (pinfunction "C_1") (pintype "passive"))
    )
    (net (code "23") (name "Net-(L_12V-PadA)") (class "Default")
      (node (ref "L_12V") (pin "A") (pinfunction "A_A") (pintype "passive"))
      (node (ref "RLD3") (pin "1") (pinfunction "1_1") (pintype "passive"))
    )
    (net (code "24") (name "Net-(L_VBAT-PadA)") (class "Default")
      (node (ref "L_VBAT") (pin "A") (pinfunction "A_A") (pintype "passive"))
      (node (ref "RLD1") (pin "1") (pinfunction "1_1") (pintype "passive"))
    )
    (net (code "25") (name "Net-(QA_H5-G)") (class "Default")
      (node (ref "QA_H5") (pin "1") (pinfunction "G_1") (pintype "bidirectional"))
      (node (ref "RG7") (pin "1") (pinfunction "1_1") (pintype "passive"))
      (node (ref "RGS7") (pin "1") (pinfunction "1_1") (pintype "passive"))
    )
    (net (code "26") (name "Net-(QA_H6-G)") (class "Default")
      (node (ref "QA_H6") (pin "1") (pinfunction "G_1") (pintype "bidirectional"))
      (node (ref "RG8") (pin "1") (pinfunction "1_1") (pintype "passive"))
      (node (ref "RGS8") (pin "1") (pinfunction "1_1") (pintype "passive"))
    )
    (net (code "27") (name "Net-(QA_L5-G)") (class "Default")
      (node (ref "QA_L5") (pin "1") (pinfunction "G_1") (pintype "bidirectional"))
      (node (ref "RG5") (pin "1") (pinfunction "1_1") (pintype "passive"))
      (node (ref "RGS5") (pin "1") (pinfunction "1_1") (pintype "passive"))
    )
    (net (code "28") (name "Net-(QA_L6-G)") (class "Default")
      (node (ref "QA_L6") (pin "1") (pinfunction "G_1") (pintype "bidirectional"))
      (node (ref "RG6") (pin "1") (pinfunction "1_1") (pintype "passive"))
      (node (ref "RGS6") (pin "1") (pinfunction "1_1") (pintype "passive"))
    )
    (net (code "29") (name "OUTA_H") (class "Default")
      (node (ref "DRVR_X") (pin "7") (pinfunction "7/DRV_HI_7") (pintype "bidirectional"))
      (node (ref "DZ15V1") (pin "2") (pinfunction "A_2") (pintype "passive"))
      (node (ref "DZ24V1") (pin "2") (pinfunction "A_2") (pintype "passive"))
      (node (ref "OUTH") (pin "P$1") (pinfunction "P$1_P$1") (pintype "bidirectional"))
      (node (ref "RG7") (pin "2") (pinfunction "2_2") (pintype "passive"))
      (node (ref "RG8") (pin "2") (pinfunction "2_2") (pintype "passive"))
      (node (ref "TP-OUTAH") (pin "P1") (pinfunction "P$1_P1") (pintype "bidirectional"))
    )
    (net (code "30") (name "OUTA_L") (class "Default")
      (node (ref "DRVR_X") (pin "4") (pinfunction "4/DRV_LO_4") (pintype "bidirectional"))
      (node (ref "DZ15V3") (pin "2") (pinfunction "A_2") (pintype "passive"))
      (node (ref "DZ24V9") (pin "2") (pinfunction "A_2") (pintype "passive"))
      (node (ref "OUTL") (pin "P$1") (pinfunction "P$1_P$1") (pintype "bidirectional"))
      (node (ref "RG5") (pin "2") (pinfunction "2_2") (pintype "passive"))
      (node (ref "RG6") (pin "2") (pinfunction "2_2") (pintype "passive"))
      (node (ref "TP-OUTAL") (pin "P1") (pinfunction "P$1_P1") (pintype "bidirectional"))
    )
    (net (code "31") (name "VBOOT") (class "Default")
      (node (ref "CBOOT1") (pin "1") (pinfunction "1_1") (pintype "passive"))
      (node (ref "DBOOT1") (pin "C") (pinfunction "C_C") (pintype "passive"))
      (node (ref "DRVR_X") (pin "8") (pinfunction "8/VBOOT_8") (pintype "bidirectional"))
    )
    (net (code "32") (name "VDDA") (class "Default")
      (node (ref "CHV1") (pin "1") (pinfunction "1_1") (pintype "passive"))
      (node (ref "CHV2") (pin "1") (pinfunction "1_1") (pintype "passive"))
      (node (ref "CVH3") (pin "1") (pinfunction "1_1") (pintype "passive"))
      (node (ref "CVH4") (pin "1") (pinfunction "1_1") (pintype "passive"))
      (node (ref "DOV3") (pin "A") (pinfunction "A_A") (pintype "passive"))
      (node (ref "J_BATT/GND") (pin "1") (pinfunction "1_1") (pintype "passive"))
      (node (ref "J_BATT/GND") (pin "2") (pinfunction "2_2") (pintype "passive"))
      (node (ref "J_BATT/GND") (pin "3") (pinfunction "3_3") (pintype "passive"))
      (node (ref "J_BATT/GND") (pin "4") (pinfunction "4_4") (pintype "passive"))
      (node (ref "QA_H5") (pin "2") (pinfunction "D_2") (pintype "bidirectional"))
      (node (ref "QA_H6") (pin "2") (pinfunction "D_2") (pintype "bidirectional"))
      (node (ref "RLD1") (pin "2") (pinfunction "2_2") (pintype "passive"))
    )
    (net (code "33") (name "VSS_A") (class "Default")
      (node (ref "CBOOT1") (pin "2") (pinfunction "2_2") (pintype "passive"))
      (node (ref "DOV4") (pin "A") (pinfunction "A_A") (pintype "passive"))
      (node (ref "DRVR_X") (pin "6") (pinfunction "6/BRIDGE_6") (pintype "bidirectional"))
      (node (ref "DZ15V2") (pin "2") (pinfunction "A_2") (pintype "passive"))
      (node (ref "J_-VLOAD") (pin "1") (pinfunction "1_1") (pintype "passive"))
      (node (ref "J_-VLOAD") (pin "2") (pinfunction "2_2") (pintype "passive"))
      (node (ref "J_-VLOAD") (pin "3") (pinfunction "3_3") (pintype "passive"))
      (node (ref "J_-VLOAD") (pin "4") (pinfunction "4_4") (pintype "passive"))
      (node (ref "QA_H5") (pin "3") (pinfunction "S_3") (pintype "bidirectional"))
      (node (ref "QA_H6") (pin "3") (pinfunction "S_3") (pintype "bidirectional"))
      (node (ref "QA_L5") (pin "2") (pinfunction "D_2") (pintype "bidirectional"))
      (node (ref "QA_L6") (pin "2") (pinfunction "D_2") (pintype "bidirectional"))
      (node (ref "RGS7") (pin "2") (pinfunction "2_2") (pintype "passive"))
      (node (ref "RGS8") (pin "2") (pinfunction "2_2") (pintype "passive"))
      (node (ref "SRC1") (pin "P$1") (pinfunction "P$1_P$1") (pintype "bidirectional"))
    )
    (net (code "34") (name "unconnected-(J_-VLOAD-Pad5)") (class "Default")
      (node (ref "J_-VLOAD") (pin "5") (pinfunction "5_5") (pintype "passive"))
    )
    (net (code "35") (name "unconnected-(J_-VLOAD-Pad6)") (class "Default")
      (node (ref "J_-VLOAD") (pin "6") (pinfunction "6_6") (pintype "passive"))
    )
    (net (code "36") (name "unconnected-(J_-VLOAD-Pad7)") (class "Default")
      (node (ref "J_-VLOAD") (pin "7") (pinfunction "7_7") (pintype "passive"))
    )
    (net (code "37") (name "unconnected-(J_-VLOAD-Pad8)") (class "Default")
      (node (ref "J_-VLOAD") (pin "8") (pinfunction "8_8") (pintype "passive"))
    )
    (net (code "38") (name "unconnected-(J_BATT/GND-Pad5)") (class "Default")
      (node (ref "J_BATT/GND") (pin "5") (pinfunction "5_5") (pintype "passive"))
    )
    (net (code "39") (name "unconnected-(J_BATT/GND-Pad6)") (class "Default")
      (node (ref "J_BATT/GND") (pin "6") (pinfunction "6_6") (pintype "passive"))
    )
    (net (code "40") (name "unconnected-(MS1-Pad1)") (class "Default")
      (node (ref "MS1") (pin "1") (pinfunction "1_1") (pintype "passive"))
    )
    (net (code "41") (name "unconnected-(MS2-Pad1)") (class "Default")
      (node (ref "MS2") (pin "1") (pinfunction "1_1") (pintype "passive"))
    )
    (net (code "42") (name "unconnected-(MS3-Pad1)") (class "Default")
      (node (ref "MS3") (pin "1") (pinfunction "1_1") (pintype "passive"))
    )
  )
)
